# BOTTOM.net
KiCad netlist of a schematic drawn in Altium Designer
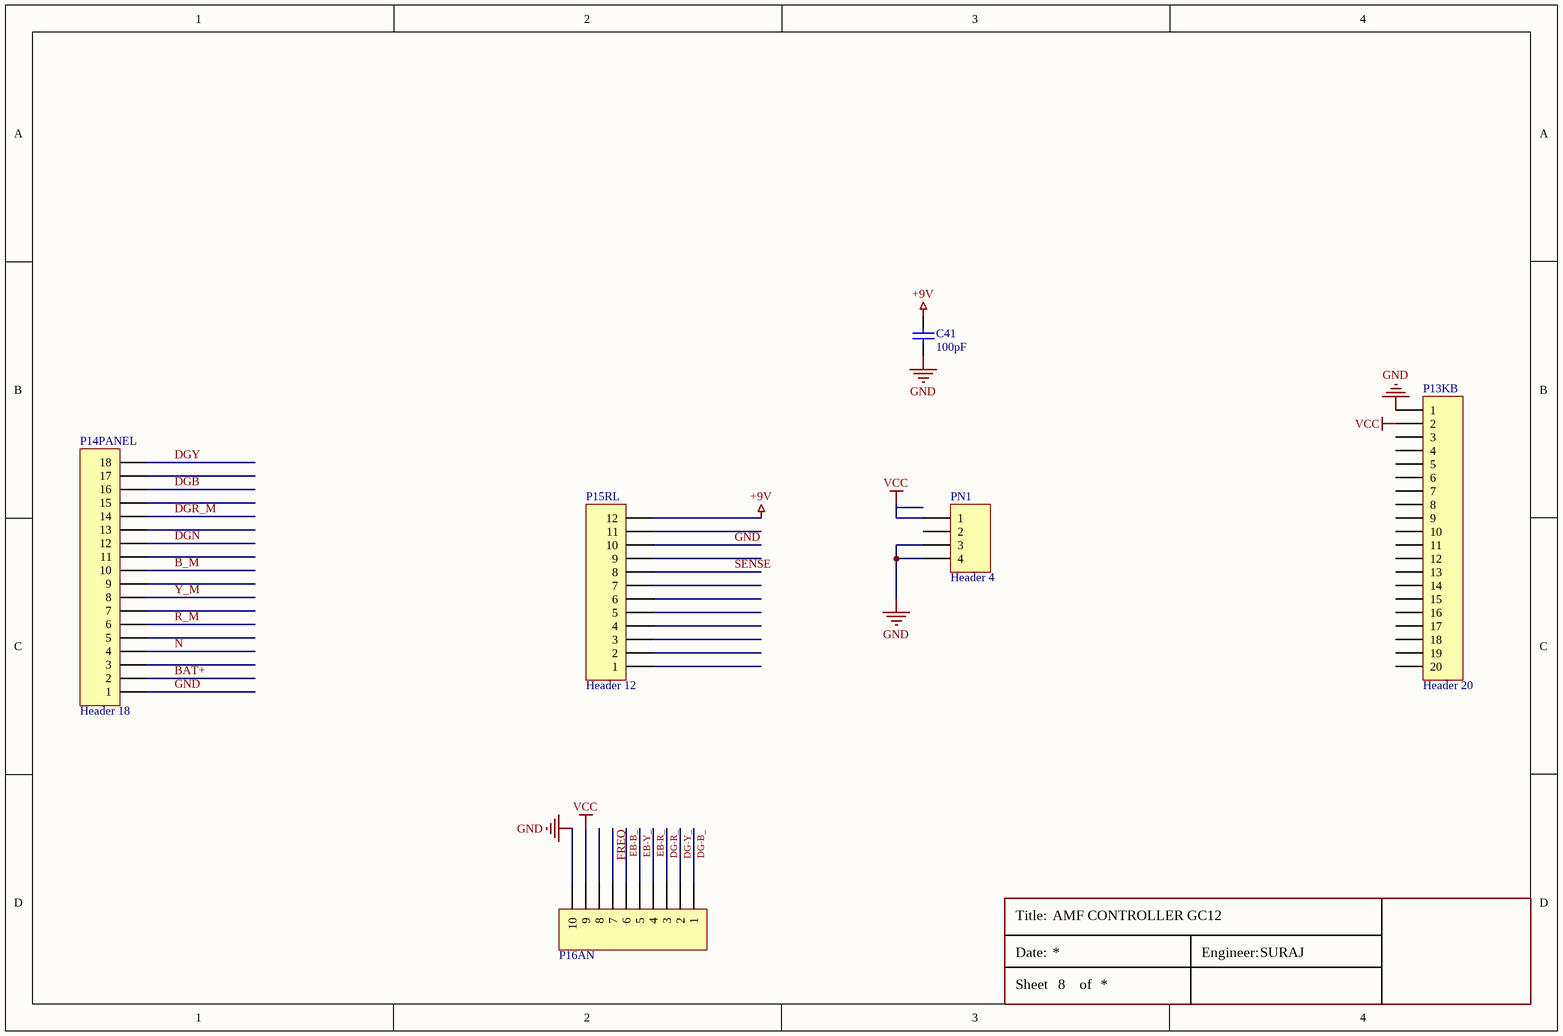
[diagram p0: BOTTOM.SchDoc]

(export (version "E")
  (design (tool "Eeschema 10.0.6"))
  (components
    (comp (ref "C41")
      (value "100pF")
      (footprint "C1206VW")
      (description "Capacitor")
      (fields (field (name "Comment") ".1uF 1206") (field (name "PUBLISHER") "Altium Limited"))
      (libsource (lib "Miscellaneous Devices") (part "Cap"))
    )
    (comp (ref "P13KB")
      (value "Header 20")
      (footprint "HDR1X20_BURGE_F")
      (description "Header, 20-Pin")
      (fields (field (name "PUBLISHER") "Altium Limited"))
      (libsource (lib "Miscellaneous Connectors") (part "Header 20"))
    )
    (comp (ref "P14PANEL")
      (value "Header 18")
      (footprint "HDR1X18_BURGE_F")
      (description "Header, 18-Pin")
      (fields (field (name "PUBLISHER") "Altium Limited"))
      (libsource (lib "Miscellaneous Connectors") (part "Header 18"))
    )
    (comp (ref "P15RL")
      (value "Header 12")
      (footprint "HDR1X12_BURGE_F")
      (description "Header, 12-Pin")
      (fields (field (name "PUBLISHER") "Altium Limited"))
      (libsource (lib "Miscellaneous Connectors") (part "Header 12"))
    )
    (comp (ref "P16AN")
      (value "Header 10")
      (footprint "HDR1X10_BURGE_F")
      (description "Header, 10-Pin")
      (fields (field (name "PUBLISHER") "Altium Limited"))
      (libsource (lib "Miscellaneous Connectors") (part "Header 10"))
    )
    (comp (ref "PN1")
      (value "Header 4")
      (footprint "HDR1X4_BURGE_F")
      (description "Header, 4-Pin")
      (fields (field (name "PUBLISHER") "Altium Limited"))
      (libsource (lib "Miscellaneous Connectors") (part "Header 4"))
    )
  )
  (nets
    (net (code "1") (name "+9V") (class "Default")
      (node (ref "C41") (pin "2") (pinfunction "2_2") (pintype "passive"))
      (node (ref "P15RL") (pin "12") (pinfunction "12_12") (pintype "passive"))
    )
    (net (code "2") (name "/BAT+") (class "Default")
      (node (ref "P14PANEL") (pin "2") (pinfunction "2_2") (pintype "passive"))
    )
    (net (code "3") (name "/B_M") (class "Default")
      (node (ref "P14PANEL") (pin "10") (pinfunction "10_10") (pintype "passive"))
    )
    (net (code "4") (name "/DG-B_") (class "Default")
      (node (ref "P16AN") (pin "1") (pinfunction "1_1") (pintype "passive"))
    )
    (net (code "5") (name "/DG-R_") (class "Default")
      (node (ref "P16AN") (pin "3") (pinfunction "3_3") (pintype "passive"))
    )
    (net (code "6") (name "/DG-Y_") (class "Default")
      (node (ref "P16AN") (pin "2") (pinfunction "2_2") (pintype "passive"))
    )
    (net (code "7") (name "/DGB") (class "Default")
      (node (ref "P14PANEL") (pin "16") (pinfunction "16_16") (pintype "passive"))
    )
    (net (code "8") (name "/DGN") (class "Default")
      (node (ref "P14PANEL") (pin "12") (pinfunction "12_12") (pintype "passive"))
    )
    (net (code "9") (name "/DGR_M") (class "Default")
      (node (ref "P14PANEL") (pin "14") (pinfunction "14_14") (pintype "passive"))
    )
    (net (code "10") (name "/DGY") (class "Default")
      (node (ref "P14PANEL") (pin "18") (pinfunction "18_18") (pintype "passive"))
    )
    (net (code "11") (name "/EB-B_") (class "Default")
      (node (ref "P16AN") (pin "6") (pinfunction "6_6") (pintype "passive"))
    )
    (net (code "12") (name "/EB-R_") (class "Default")
      (node (ref "P16AN") (pin "4") (pinfunction "4_4") (pintype "passive"))
    )
    (net (code "13") (name "/EB-Y_") (class "Default")
      (node (ref "P16AN") (pin "5") (pinfunction "5_5") (pintype "passive"))
    )
    (net (code "14") (name "/FREQ") (class "Default")
      (node (ref "P16AN") (pin "7") (pinfunction "7_7") (pintype "passive"))
    )
    (net (code "15") (name "/N") (class "Default")
      (node (ref "P14PANEL") (pin "4") (pinfunction "4_4") (pintype "passive"))
    )
    (net (code "16") (name "/R_M") (class "Default")
      (node (ref "P14PANEL") (pin "6") (pinfunction "6_6") (pintype "passive"))
    )
    (net (code "17") (name "/SENSE") (class "Default")
      (node (ref "P15RL") (pin "8") (pinfunction "8_8") (pintype "passive"))
    )
    (net (code "18") (name "/Y_M") (class "Default")
      (node (ref "P14PANEL") (pin "8") (pinfunction "8_8") (pintype "passive"))
    )
    (net (code "19") (name "GND") (class "Default")
      (node (ref "C41") (pin "1") (pinfunction "1_1") (pintype "passive"))
      (node (ref "P13KB") (pin "1") (pinfunction "1_1") (pintype "passive"))
      (node (ref "P14PANEL") (pin "1") (pinfunction "1_1") (pintype "passive"))
      (node (ref "P15RL") (pin "10") (pinfunction "10_10") (pintype "passive"))
      (node (ref "P16AN") (pin "10") (pinfunction "10_10") (pintype "passive"))
      (node (ref "PN1") (pin "3") (pinfunction "3_3") (pintype "passive"))
      (node (ref "PN1") (pin "4") (pinfunction "4_4") (pintype "passive"))
    )
    (net (code "20") (name "VCC") (class "Default")
      (node (ref "P13KB") (pin "2") (pinfunction "2_2") (pintype "passive"))
      (node (ref "P16AN") (pin "9") (pinfunction "9_9") (pintype "passive"))
      (node (ref "PN1") (pin "1") (pinfunction "1_1") (pintype "passive"))
    )
    (net (code "21") (name "unconnected-(P13KB-Pad3)") (class "Default")
      (node (ref "P13KB") (pin "3") (pinfunction "3_3") (pintype "passive"))
    )
    (net (code "22") (name "unconnected-(P13KB-Pad4)") (class "Default")
      (node (ref "P13KB") (pin "4") (pinfunction "4_4") (pintype "passive"))
    )
    (net (code "23") (name "unconnected-(P13KB-Pad5)") (class "Default")
      (node (ref "P13KB") (pin "5") (pinfunction "5_5") (pintype "passive"))
    )
    (net (code "24") (name "unconnected-(P13KB-Pad6)") (class "Default")
      (node (ref "P13KB") (pin "6") (pinfunction "6_6") (pintype "passive"))
    )
    (net (code "25") (name "unconnected-(P13KB-Pad7)") (class "Default")
      (node (ref "P13KB") (pin "7") (pinfunction "7_7") (pintype "passive"))
    )
    (net (code "26") (name "unconnected-(P13KB-Pad8)") (class "Default")
      (node (ref "P13KB") (pin "8") (pinfunction "8_8") (pintype "passive"))
    )
    (net (code "27") (name "unconnected-(P13KB-Pad9)") (class "Default")
      (node (ref "P13KB") (pin "9") (pinfunction "9_9") (pintype "passive"))
    )
    (net (code "28") (name "unconnected-(P13KB-Pad10)") (class "Default")
      (node (ref "P13KB") (pin "10") (pinfunction "10_10") (pintype "passive"))
    )
    (net (code "29") (name "unconnected-(P13KB-Pad11)") (class "Default")
      (node (ref "P13KB") (pin "11") (pinfunction "11_11") (pintype "passive"))
    )
    (net (code "30") (name "unconnected-(P13KB-Pad12)") (class "Default")
      (node (ref "P13KB") (pin "12") (pinfunction "12_12") (pintype "passive"))
    )
    (net (code "31") (name "unconnected-(P13KB-Pad13)") (class "Default")
      (node (ref "P13KB") (pin "13") (pinfunction "13_13") (pintype "passive"))
    )
    (net (code "32") (name "unconnected-(P13KB-Pad14)") (class "Default")
      (node (ref "P13KB") (pin "14") (pinfunction "14_14") (pintype "passive"))
    )
    (net (code "33") (name "unconnected-(P13KB-Pad15)") (class "Default")
      (node (ref "P13KB") (pin "15") (pinfunction "15_15") (pintype "passive"))
    )
    (net (code "34") (name "unconnected-(P13KB-Pad16)") (class "Default")
      (node (ref "P13KB") (pin "16") (pinfunction "16_16") (pintype "passive"))
    )
    (net (code "35") (name "unconnected-(P13KB-Pad17)") (class "Default")
      (node (ref "P13KB") (pin "17") (pinfunction "17_17") (pintype "passive"))
    )
    (net (code "36") (name "unconnected-(P13KB-Pad18)") (class "Default")
      (node (ref "P13KB") (pin "18") (pinfunction "18_18") (pintype "passive"))
    )
    (net (code "37") (name "unconnected-(P13KB-Pad19)") (class "Default")
      (node (ref "P13KB") (pin "19") (pinfunction "19_19") (pintype "passive"))
    )
    (net (code "38") (name "unconnected-(P13KB-Pad20)") (class "Default")
      (node (ref "P13KB") (pin "20") (pinfunction "20_20") (pintype "passive"))
    )
    (net (code "39") (name "unconnected-(P14PANEL-Pad3)") (class "Default")
      (node (ref "P14PANEL") (pin "3") (pinfunction "3_3") (pintype "passive"))
    )
    (net (code "40") (name "unconnected-(P14PANEL-Pad5)") (class "Default")
      (node (ref "P14PANEL") (pin "5") (pinfunction "5_5") (pintype "passive"))
    )
    (net (code "41") (name "unconnected-(P14PANEL-Pad7)") (class "Default")
      (node (ref "P14PANEL") (pin "7") (pinfunction "7_7") (pintype "passive"))
    )
    (net (code "42") (name "unconnected-(P14PANEL-Pad9)") (class "Default")
      (node (ref "P14PANEL") (pin "9") (pinfunction "9_9") (pintype "passive"))
    )
    (net (code "43") (name "unconnected-(P14PANEL-Pad11)") (class "Default")
      (node (ref "P14PANEL") (pin "11") (pinfunction "11_11") (pintype "passive"))
    )
    (net (code "44") (name "unconnected-(P14PANEL-Pad13)") (class "Default")
      (node (ref "P14PANEL") (pin "13") (pinfunction "13_13") (pintype "passive"))
    )
    (net (code "45") (name "unconnected-(P14PANEL-Pad15)") (class "Default")
      (node (ref "P14PANEL") (pin "15") (pinfunction "15_15") (pintype "passive"))
    )
    (net (code "46") (name "unconnected-(P14PANEL-Pad17)") (class "Default")
      (node (ref "P14PANEL") (pin "17") (pinfunction "17_17") (pintype "passive"))
    )
    (net (code "47") (name "unconnected-(P15RL-Pad1)") (class "Default")
      (node (ref "P15RL") (pin "1") (pinfunction "1_1") (pintype "passive"))
    )
    (net (code "48") (name "unconnected-(P15RL-Pad2)") (class "Default")
      (node (ref "P15RL") (pin "2") (pinfunction "2_2") (pintype "passive"))
    )
    (net (code "49") (name "unconnected-(P15RL-Pad3)") (class "Default")
      (node (ref "P15RL") (pin "3") (pinfunction "3_3") (pintype "passive"))
    )
    (net (code "50") (name "unconnected-(P15RL-Pad4)") (class "Default")
      (node (ref "P15RL") (pin "4") (pinfunction "4_4") (pintype "passive"))
    )
    (net (code "51") (name "unconnected-(P15RL-Pad5)") (class "Default")
      (node (ref "P15RL") (pin "5") (pinfunction "5_5") (pintype "passive"))
    )
    (net (code "52") (name "unconnected-(P15RL-Pad6)") (class "Default")
      (node (ref "P15RL") (pin "6") (pinfunction "6_6") (pintype "passive"))
    )
    (net (code "53") (name "unconnected-(P15RL-Pad7)") (class "Default")
      (node (ref "P15RL") (pin "7") (pinfunction "7_7") (pintype "passive"))
    )
    (net (code "54") (name "unconnected-(P15RL-Pad9)") (class "Default")
      (node (ref "P15RL") (pin "9") (pinfunction "9_9") (pintype "passive"))
    )
    (net (code "55") (name "unconnected-(P15RL-Pad11)") (class "Default")
      (node (ref "P15RL") (pin "11") (pinfunction "11_11") (pintype "passive"))
    )
    (net (code "56") (name "unconnected-(P16AN-Pad8)") (class "Default")
      (node (ref "P16AN") (pin "8") (pinfunction "8_8") (pintype "passive"))
    )
    (net (code "57") (name "unconnected-(PN1-Pad2)") (class "Default")
      (node (ref "PN1") (pin "2") (pinfunction "2_2") (pintype "passive"))
    )
  )
)
